# ProPrj___2025-09-23.net
KiCad netlist of a schematic drawn in EasyEDA Pro
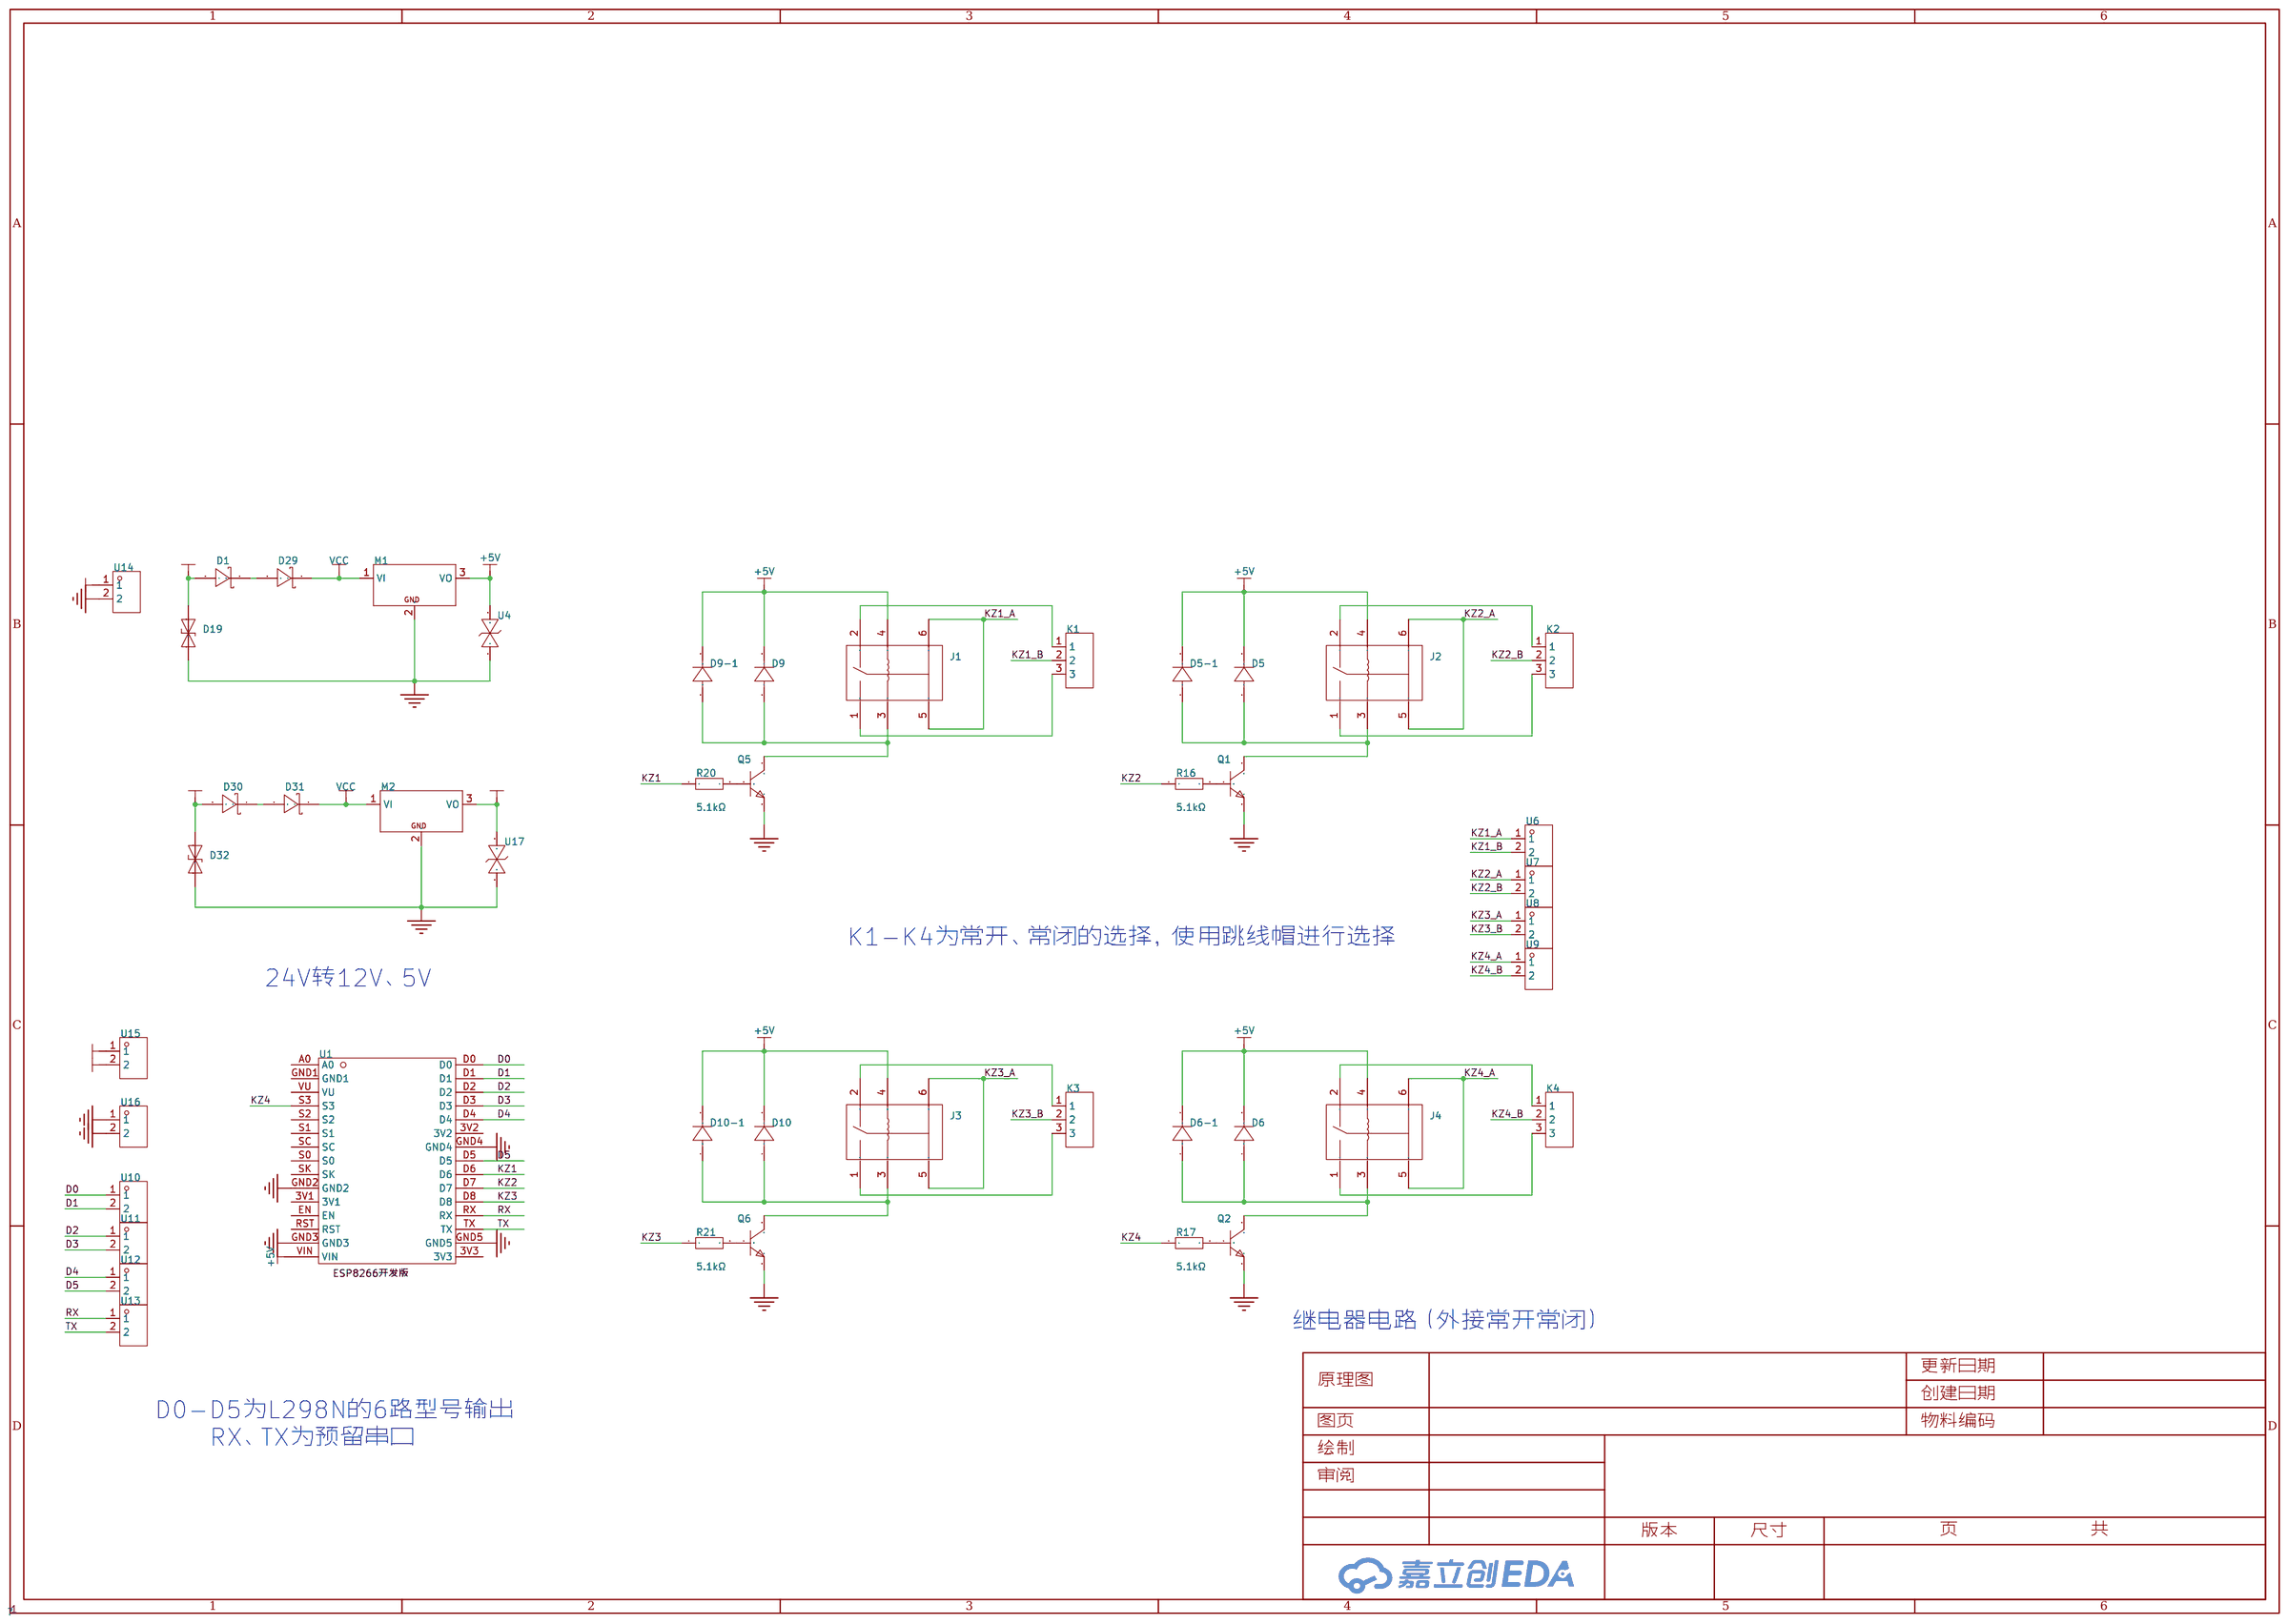
[diagram p0: schematic sheet]

(export (version "E")
  (design (tool "Eeschema 10.0.6"))
  (components
    (comp (ref "D1")
      (value "SS14")
      (footprint "easyedapro:SMA_L4.2-W2.6-LS5.0-RD_1")
      (description "二极管配置:独立式;正向压降(Vf):550mV@1A;直流反向耐压(Vr):40V;整流电流:1A;")
      (fields (field (name "Manufacturer") "MDD(辰达半导体)"))
      (libsource (lib "easyedapro") (part "SS14"))
    )
    (comp (ref "D5")
      (value "1N4148WS")
      (footprint "easyedapro:SOD-323_L1.7-W1.3-LS2.5-FD")
      (description "二极管配置:独立式;正向压降(Vf):1.25V@150mA;直流反向耐压(Vr):100V;整流电流:150mA;反向恢复时间(Trr):4ns;")
      (fields (field (name "Manufacturer") "宏嘉诚"))
      (libsource (lib "easyedapro") (part "1N4148WS_C7420319"))
    )
    (comp (ref "D5-1")
      (value "1N4148WS")
      (footprint "easyedapro:SOD-323_L1.7-W1.3-LS2.5-FD")
      (description "二极管配置:独立式;正向压降(Vf):1.25V@150mA;直流反向耐压(Vr):100V;整流电流:150mA;反向恢复时间(Trr):4ns;")
      (fields (field (name "Manufacturer") "宏嘉诚"))
      (libsource (lib "easyedapro") (part "1N4148WS_C7420319"))
    )
    (comp (ref "D6")
      (value "1N4148WS")
      (footprint "easyedapro:SOD-323_L1.7-W1.3-LS2.5-FD")
      (description "二极管配置:独立式;正向压降(Vf):1.25V@150mA;直流反向耐压(Vr):100V;整流电流:150mA;反向恢复时间(Trr):4ns;")
      (fields (field (name "Manufacturer") "宏嘉诚"))
      (libsource (lib "easyedapro") (part "1N4148WS_C7420319"))
    )
    (comp (ref "D6-1")
      (value "1N4148WS")
      (footprint "easyedapro:SOD-323_L1.7-W1.3-LS2.5-FD")
      (description "二极管配置:独立式;正向压降(Vf):1.25V@150mA;直流反向耐压(Vr):100V;整流电流:150mA;反向恢复时间(Trr):4ns;")
      (fields (field (name "Manufacturer") "宏嘉诚"))
      (libsource (lib "easyedapro") (part "1N4148WS_C7420319"))
    )
    (comp (ref "D9")
      (value "1N4148WS")
      (footprint "easyedapro:SOD-323_L1.7-W1.3-LS2.5-FD")
      (description "二极管配置:独立式;正向压降(Vf):1.25V@150mA;直流反向耐压(Vr):100V;整流电流:150mA;反向恢复时间(Trr):4ns;")
      (fields (field (name "Manufacturer") "宏嘉诚"))
      (libsource (lib "easyedapro") (part "1N4148WS_C7420319"))
    )
    (comp (ref "D9-1")
      (value "1N4148WS")
      (footprint "easyedapro:SOD-323_L1.7-W1.3-LS2.5-FD")
      (description "二极管配置:独立式;正向压降(Vf):1.25V@150mA;直流反向耐压(Vr):100V;整流电流:150mA;反向恢复时间(Trr):4ns;")
      (fields (field (name "Manufacturer") "宏嘉诚"))
      (libsource (lib "easyedapro") (part "1N4148WS_C7420319"))
    )
    (comp (ref "D10")
      (value "1N4148WS")
      (footprint "easyedapro:SOD-323_L1.7-W1.3-LS2.5-FD")
      (description "二极管配置:独立式;正向压降(Vf):1.25V@150mA;直流反向耐压(Vr):100V;整流电流:150mA;反向恢复时间(Trr):4ns;")
      (fields (field (name "Manufacturer") "宏嘉诚"))
      (libsource (lib "easyedapro") (part "1N4148WS_C7420319"))
    )
    (comp (ref "D10-1")
      (value "1N4148WS")
      (footprint "easyedapro:SOD-323_L1.7-W1.3-LS2.5-FD")
      (description "二极管配置:独立式;正向压降(Vf):1.25V@150mA;直流反向耐压(Vr):100V;整流电流:150mA;反向恢复时间(Trr):4ns;")
      (fields (field (name "Manufacturer") "宏嘉诚"))
      (libsource (lib "easyedapro") (part "1N4148WS_C7420319"))
    )
    (comp (ref "D19")
      (value "SMCJ33CA")
      (footprint "easyedapro:SMC_L6.9-W5.9-LS7.9-BI")
      (description "反向截止电压(Vrwm):33V;最大钳位电压:53.3V;峰值脉冲电流(Ipp):28.2A;击穿电压:36.7V;")
      (fields (field (name "Manufacturer") "JJW(捷捷微)"))
      (libsource (lib "easyedapro") (part "SMCJ33CA_C356787"))
    )
    (comp (ref "D29")
      (value "SS14")
      (footprint "easyedapro:SMA_L4.2-W2.6-LS5.0-RD_1")
      (description "二极管配置:独立式;正向压降(Vf):550mV@1A;直流反向耐压(Vr):40V;整流电流:1A;")
      (fields (field (name "Manufacturer") "MDD(辰达半导体)"))
      (libsource (lib "easyedapro") (part "SS14"))
    )
    (comp (ref "D30")
      (value "SS14")
      (footprint "easyedapro:SMA_L4.2-W2.6-LS5.0-RD_1")
      (description "二极管配置:独立式;正向压降(Vf):550mV@1A;直流反向耐压(Vr):40V;整流电流:1A;")
      (fields (field (name "Manufacturer") "MDD(辰达半导体)"))
      (libsource (lib "easyedapro") (part "SS14"))
    )
    (comp (ref "D31")
      (value "SS14")
      (footprint "easyedapro:SMA_L4.2-W2.6-LS5.0-RD_1")
      (description "二极管配置:独立式;正向压降(Vf):550mV@1A;直流反向耐压(Vr):40V;整流电流:1A;")
      (fields (field (name "Manufacturer") "MDD(辰达半导体)"))
      (libsource (lib "easyedapro") (part "SS14"))
    )
    (comp (ref "D32")
      (value "SMCJ33CA")
      (footprint "easyedapro:SMC_L6.9-W5.9-LS7.9-BI")
      (description "反向截止电压(Vrwm):33V;最大钳位电压:53.3V;峰值脉冲电流(Ipp):28.2A;击穿电压:36.7V;")
      (fields (field (name "Manufacturer") "JJW(捷捷微)"))
      (libsource (lib "easyedapro") (part "SMCJ33CA_C356787"))
    )
    (comp (ref "J1")
      (value "HK4100F-DC5V-SHG")
      (footprint "easyedapro:RELAY-TH_HK4100F-DC5V-SHG")
      (description "线圈电压:-;触点形式:-;触点容量(电阻负载):-;最大切换电压:-;最大切换电流:-;")
      (fields (field (name "Manufacturer") "汇科"))
      (libsource (lib "easyedapro") (part "HK4100F-DC5V-SHG"))
    )
    (comp (ref "J2")
      (value "HK4100F-DC5V-SHG")
      (footprint "easyedapro:RELAY-TH_HK4100F-DC5V-SHG")
      (description "线圈电压:-;触点形式:-;触点容量(电阻负载):-;最大切换电压:-;最大切换电流:-;")
      (fields (field (name "Manufacturer") "汇科"))
      (libsource (lib "easyedapro") (part "HK4100F-DC5V-SHG"))
    )
    (comp (ref "J3")
      (value "HK4100F-DC5V-SHG")
      (footprint "easyedapro:RELAY-TH_HK4100F-DC5V-SHG")
      (description "线圈电压:-;触点形式:-;触点容量(电阻负载):-;最大切换电压:-;最大切换电流:-;")
      (fields (field (name "Manufacturer") "汇科"))
      (libsource (lib "easyedapro") (part "HK4100F-DC5V-SHG"))
    )
    (comp (ref "J4")
      (value "HK4100F-DC5V-SHG")
      (footprint "easyedapro:RELAY-TH_HK4100F-DC5V-SHG")
      (description "线圈电压:-;触点形式:-;触点容量(电阻负载):-;最大切换电压:-;最大切换电流:-;")
      (fields (field (name "Manufacturer") "汇科"))
      (libsource (lib "easyedapro") (part "HK4100F-DC5V-SHG"))
    )
    (comp (ref "K1")
      (value "PZ254V-11-03P")
      (footprint "easyedapro:HDR-TH_3P-P2.54-V-M")
      (fields (field (name "Manufacturer") "XFCN(兴飞)"))
      (libsource (lib "easyedapro") (part "PZ254V-11-03P_C2937625"))
    )
    (comp (ref "K2")
      (value "PZ254V-11-03P")
      (footprint "easyedapro:HDR-TH_3P-P2.54-V-M")
      (fields (field (name "Manufacturer") "XFCN(兴飞)"))
      (libsource (lib "easyedapro") (part "PZ254V-11-03P_C2937625"))
    )
    (comp (ref "K3")
      (value "PZ254V-11-03P")
      (footprint "easyedapro:HDR-TH_3P-P2.54-V-M")
      (fields (field (name "Manufacturer") "XFCN(兴飞)"))
      (libsource (lib "easyedapro") (part "PZ254V-11-03P_C2937625"))
    )
    (comp (ref "K4")
      (value "PZ254V-11-03P")
      (footprint "easyedapro:HDR-TH_3P-P2.54-V-M")
      (fields (field (name "Manufacturer") "XFCN(兴飞)"))
      (libsource (lib "easyedapro") (part "PZ254V-11-03P_C2937625"))
    )
    (comp (ref "M1")
      (value "K78L05-1000R3")
      (fields (field (name "Manufacturer") "MORNSUN(金升阳)"))
      (libsource (lib "easyedapro") (part "K7805-2000L"))
    )
    (comp (ref "M2")
      (value "K78L12-1000R3")
      (fields (field (name "Manufacturer") "MORNSUN(金升阳)"))
      (libsource (lib "easyedapro") (part "K7805-2000L"))
    )
    (comp (ref "Q1")
      (value "S9014")
      (footprint "easyedapro:SOT-23-3_L2.9-W1.3-P1.90-LS2.4-BR")
      (description "晶体管类型:NPN;集电极电流(Ic):100mA;集射极击穿电压(Vceo):45V;耗散功率(Pd):200mW;直流电流增益(hFE):200@1mA,5V;")
      (fields (field (name "Manufacturer") "CJ(江苏长电/长晶)"))
      (libsource (lib "easyedapro") (part "S9014LT1 (S9014 J6)"))
    )
    (comp (ref "Q2")
      (value "S9014")
      (footprint "easyedapro:SOT-23-3_L2.9-W1.3-P1.90-LS2.4-BR")
      (description "晶体管类型:NPN;集电极电流(Ic):100mA;集射极击穿电压(Vceo):45V;耗散功率(Pd):200mW;直流电流增益(hFE):200@1mA,5V;")
      (fields (field (name "Manufacturer") "CJ(江苏长电/长晶)"))
      (libsource (lib "easyedapro") (part "S9014LT1 (S9014 J6)"))
    )
    (comp (ref "Q5")
      (value "S9014")
      (footprint "easyedapro:SOT-23-3_L2.9-W1.3-P1.90-LS2.4-BR")
      (description "晶体管类型:NPN;集电极电流(Ic):100mA;集射极击穿电压(Vceo):45V;耗散功率(Pd):200mW;直流电流增益(hFE):200@1mA,5V;")
      (fields (field (name "Manufacturer") "CJ(江苏长电/长晶)"))
      (libsource (lib "easyedapro") (part "S9014LT1 (S9014 J6)"))
    )
    (comp (ref "Q6")
      (value "S9014")
      (footprint "easyedapro:SOT-23-3_L2.9-W1.3-P1.90-LS2.4-BR")
      (description "晶体管类型:NPN;集电极电流(Ic):100mA;集射极击穿电压(Vceo):45V;耗散功率(Pd):200mW;直流电流增益(hFE):200@1mA,5V;")
      (fields (field (name "Manufacturer") "CJ(江苏长电/长晶)"))
      (libsource (lib "easyedapro") (part "S9014LT1 (S9014 J6)"))
    )
    (comp (ref "R16")
      (value "5.1kΩ")
      (fields
        (field (name "Manufacturer Part") "0603WAF5101T5E")
        (field (name "Manufacturer") "UNI-ROYAL(厚声)")
      )
      (libsource (lib "easyedapro") (part "电阻"))
    )
    (comp (ref "R17")
      (value "5.1kΩ")
      (fields
        (field (name "Manufacturer Part") "0603WAF5101T5E")
        (field (name "Manufacturer") "UNI-ROYAL(厚声)")
      )
      (libsource (lib "easyedapro") (part "电阻"))
    )
    (comp (ref "R20")
      (value "5.1kΩ")
      (fields
        (field (name "Manufacturer Part") "0603WAF5101T5E")
        (field (name "Manufacturer") "UNI-ROYAL(厚声)")
      )
      (libsource (lib "easyedapro") (part "电阻"))
    )
    (comp (ref "R21")
      (value "5.1kΩ")
      (fields
        (field (name "Manufacturer Part") "0603WAF5101T5E")
        (field (name "Manufacturer") "UNI-ROYAL(厚声)")
      )
      (libsource (lib "easyedapro") (part "电阻"))
    )
    (comp (ref "U1")
      (value "~")
      (footprint "easyedapro:ESP8266开发板")
      (libsource (lib "easyedapro") (part "ESP8266开发板"))
    )
    (comp (ref "U4")
      (value "SMBJ5.0CA")
      (footprint "easyedapro:SMB_L4.5-W3.6-LS5.2-BI")
      (description "极性:双向;反向截止电压(Vrwm):5V;钳位电压:9.2V;峰值脉冲电流(Ipp):65.22A;峰值脉冲功率(Ppp):600W;击穿电压:7V;")
      (fields (field (name "Manufacturer") "宏嘉诚"))
      (libsource (lib "easyedapro") (part "SMBJ5.0CA_C19077559"))
    )
    (comp (ref "U6")
      (value "KF7.62-2P(green)")
      (fields (field (name "Manufacturer") "KEFA(科发)"))
      (libsource (lib "easyedapro") (part "KF8500-8.5-2P"))
    )
    (comp (ref "U7")
      (value "KF7.62-2P(green)")
      (fields (field (name "Manufacturer") "KEFA(科发)"))
      (libsource (lib "easyedapro") (part "KF8500-8.5-2P"))
    )
    (comp (ref "U8")
      (value "KF7.62-2P(green)")
      (fields (field (name "Manufacturer") "KEFA(科发)"))
      (libsource (lib "easyedapro") (part "KF8500-8.5-2P"))
    )
    (comp (ref "U9")
      (value "KF7.62-2P(green)")
      (fields (field (name "Manufacturer") "KEFA(科发)"))
      (libsource (lib "easyedapro") (part "KF8500-8.5-2P"))
    )
    (comp (ref "U10")
      (value "KF7.62-2P(green)")
      (fields (field (name "Manufacturer") "KEFA(科发)"))
      (libsource (lib "easyedapro") (part "KF8500-8.5-2P"))
    )
    (comp (ref "U11")
      (value "KF7.62-2P(green)")
      (fields (field (name "Manufacturer") "KEFA(科发)"))
      (libsource (lib "easyedapro") (part "KF8500-8.5-2P"))
    )
    (comp (ref "U12")
      (value "KF7.62-2P(green)")
      (fields (field (name "Manufacturer") "KEFA(科发)"))
      (libsource (lib "easyedapro") (part "KF8500-8.5-2P"))
    )
    (comp (ref "U13")
      (value "KF7.62-2P(green)")
      (fields (field (name "Manufacturer") "KEFA(科发)"))
      (libsource (lib "easyedapro") (part "KF8500-8.5-2P"))
    )
    (comp (ref "U14")
      (value "KF7.62-2P(green)")
      (fields (field (name "Manufacturer") "KEFA(科发)"))
      (libsource (lib "easyedapro") (part "KF8500-8.5-2P"))
    )
    (comp (ref "U15")
      (value "KF7.62-2P(green)")
      (fields (field (name "Manufacturer") "KEFA(科发)"))
      (libsource (lib "easyedapro") (part "KF8500-8.5-2P"))
    )
    (comp (ref "U16")
      (value "KF7.62-2P(green)")
      (fields (field (name "Manufacturer") "KEFA(科发)"))
      (libsource (lib "easyedapro") (part "KF8500-8.5-2P"))
    )
    (comp (ref "U17")
      (value "SMBJ12CA")
      (footprint "easyedapro:SMB_L4.5-W3.6-LS5.2-BI")
      (description "极性:双向;反向截止电压(Vrwm):5V;钳位电压:9.2V;峰值脉冲电流(Ipp):65.22A;峰值脉冲功率(Ppp):600W;击穿电压:7V;")
      (fields (field (name "Manufacturer") "Littelfuse(美国力特)"))
      (libsource (lib "easyedapro") (part "SMBJ5.0CA_C19077559"))
    )
  )
  (nets
    (net (code "1") (name "+5V") (class "Default")
      (node (ref "D10") (pin "2") (pinfunction "K_2") (pintype "unspecified"))
      (node (ref "D10-1") (pin "2") (pinfunction "K_2") (pintype "unspecified"))
      (node (ref "D5") (pin "2") (pinfunction "K_2") (pintype "unspecified"))
      (node (ref "D5-1") (pin "2") (pinfunction "K_2") (pintype "unspecified"))
      (node (ref "D6") (pin "2") (pinfunction "K_2") (pintype "unspecified"))
      (node (ref "D6-1") (pin "2") (pinfunction "K_2") (pintype "unspecified"))
      (node (ref "D9") (pin "2") (pinfunction "K_2") (pintype "unspecified"))
      (node (ref "D9-1") (pin "2") (pinfunction "K_2") (pintype "unspecified"))
      (node (ref "J1") (pin "4") (pinfunction "4_4") (pintype "unspecified"))
      (node (ref "J2") (pin "4") (pinfunction "4_4") (pintype "unspecified"))
      (node (ref "J3") (pin "4") (pinfunction "4_4") (pintype "unspecified"))
      (node (ref "J4") (pin "4") (pinfunction "4_4") (pintype "unspecified"))
      (node (ref "M1") (pin "3") (pinfunction "VO_3") (pintype "unspecified"))
      (node (ref "U1") (pin "VIN") (pinfunction "VIN_VIN") (pintype "input"))
      (node (ref "U4") (pin "2") (pinfunction "2_2") (pintype "unspecified"))
    )
    (net (code "2") (name "+12V") (class "Default")
      (node (ref "M2") (pin "3") (pinfunction "VO_3") (pintype "unspecified"))
      (node (ref "U15") (pin "1") (pinfunction "1_1") (pintype "unspecified"))
      (node (ref "U15") (pin "2") (pinfunction "2_2") (pintype "unspecified"))
      (node (ref "U17") (pin "2") (pinfunction "2_2") (pintype "unspecified"))
    )
    (net (code "3") (name "+24V") (class "Default")
      (node (ref "D1") (pin "2") (pinfunction "A_2") (pintype "unspecified"))
      (node (ref "D19") (pin "2") (pinfunction "A_2") (pintype "unspecified"))
      (node (ref "D30") (pin "2") (pinfunction "A_2") (pintype "unspecified"))
      (node (ref "D32") (pin "2") (pinfunction "A_2") (pintype "unspecified"))
      (node (ref "U14") (pin "1") (pinfunction "1_1") (pintype "unspecified"))
    )
    (net (code "4") (name "/D0") (class "Default")
      (node (ref "U1") (pin "D0") (pinfunction "D0_D0") (pintype "input"))
      (node (ref "U10") (pin "1") (pinfunction "1_1") (pintype "unspecified"))
    )
    (net (code "5") (name "/D1") (class "Default")
      (node (ref "U1") (pin "D1") (pinfunction "D1_D1") (pintype "input"))
      (node (ref "U10") (pin "2") (pinfunction "2_2") (pintype "unspecified"))
    )
    (net (code "6") (name "/D2") (class "Default")
      (node (ref "U1") (pin "D2") (pinfunction "D2_D2") (pintype "input"))
      (node (ref "U11") (pin "1") (pinfunction "1_1") (pintype "unspecified"))
    )
    (net (code "7") (name "/D3") (class "Default")
      (node (ref "U1") (pin "D3") (pinfunction "D3_D3") (pintype "input"))
      (node (ref "U11") (pin "2") (pinfunction "2_2") (pintype "unspecified"))
    )
    (net (code "8") (name "/D4") (class "Default")
      (node (ref "U1") (pin "D4") (pinfunction "D4_D4") (pintype "input"))
      (node (ref "U12") (pin "1") (pinfunction "1_1") (pintype "unspecified"))
    )
    (net (code "9") (name "/D5") (class "Default")
      (node (ref "U1") (pin "D5") (pinfunction "D5_D5") (pintype "input"))
      (node (ref "U12") (pin "2") (pinfunction "2_2") (pintype "unspecified"))
    )
    (net (code "10") (name "/KZ1") (class "Default")
      (node (ref "R20") (pin "1") (pinfunction "1_1") (pintype "input"))
      (node (ref "U1") (pin "D6") (pinfunction "D6_D6") (pintype "input"))
    )
    (net (code "11") (name "/KZ1_A") (class "Default")
      (node (ref "J1") (pin "5") (pinfunction "5_5") (pintype "unspecified"))
      (node (ref "J1") (pin "6") (pinfunction "6_6") (pintype "unspecified"))
      (node (ref "U6") (pin "1") (pinfunction "1_1") (pintype "unspecified"))
    )
    (net (code "12") (name "/KZ1_B") (class "Default")
      (node (ref "K1") (pin "2") (pinfunction "2_2") (pintype "unspecified"))
      (node (ref "U6") (pin "2") (pinfunction "2_2") (pintype "unspecified"))
    )
    (net (code "13") (name "/KZ2") (class "Default")
      (node (ref "R16") (pin "1") (pinfunction "1_1") (pintype "input"))
      (node (ref "U1") (pin "D7") (pinfunction "D7_D7") (pintype "input"))
    )
    (net (code "14") (name "/KZ2_A") (class "Default")
      (node (ref "J2") (pin "5") (pinfunction "5_5") (pintype "unspecified"))
      (node (ref "J2") (pin "6") (pinfunction "6_6") (pintype "unspecified"))
      (node (ref "U7") (pin "1") (pinfunction "1_1") (pintype "unspecified"))
    )
    (net (code "15") (name "/KZ2_B") (class "Default")
      (node (ref "K2") (pin "2") (pinfunction "2_2") (pintype "unspecified"))
      (node (ref "U7") (pin "2") (pinfunction "2_2") (pintype "unspecified"))
    )
    (net (code "16") (name "/KZ3") (class "Default")
      (node (ref "R21") (pin "1") (pinfunction "1_1") (pintype "input"))
      (node (ref "U1") (pin "D8") (pinfunction "D8_D8") (pintype "input"))
    )
    (net (code "17") (name "/KZ3_A") (class "Default")
      (node (ref "J3") (pin "5") (pinfunction "5_5") (pintype "unspecified"))
      (node (ref "J3") (pin "6") (pinfunction "6_6") (pintype "unspecified"))
      (node (ref "U8") (pin "1") (pinfunction "1_1") (pintype "unspecified"))
    )
    (net (code "18") (name "/KZ3_B") (class "Default")
      (node (ref "K3") (pin "2") (pinfunction "2_2") (pintype "unspecified"))
      (node (ref "U8") (pin "2") (pinfunction "2_2") (pintype "unspecified"))
    )
    (net (code "19") (name "/KZ4") (class "Default")
      (node (ref "R17") (pin "1") (pinfunction "1_1") (pintype "input"))
      (node (ref "U1") (pin "S3") (pinfunction "S3_S3") (pintype "input"))
    )
    (net (code "20") (name "/KZ4_A") (class "Default")
      (node (ref "J4") (pin "5") (pinfunction "5_5") (pintype "unspecified"))
      (node (ref "J4") (pin "6") (pinfunction "6_6") (pintype "unspecified"))
      (node (ref "U9") (pin "1") (pinfunction "1_1") (pintype "unspecified"))
    )
    (net (code "21") (name "/KZ4_B") (class "Default")
      (node (ref "K4") (pin "2") (pinfunction "2_2") (pintype "unspecified"))
      (node (ref "U9") (pin "2") (pinfunction "2_2") (pintype "unspecified"))
    )
    (net (code "22") (name "/RX") (class "Default")
      (node (ref "U1") (pin "RX") (pinfunction "RX_RX") (pintype "input"))
      (node (ref "U13") (pin "1") (pinfunction "1_1") (pintype "unspecified"))
    )
    (net (code "23") (name "/TX") (class "Default")
      (node (ref "U1") (pin "TX") (pinfunction "TX_TX") (pintype "input"))
      (node (ref "U13") (pin "2") (pinfunction "2_2") (pintype "unspecified"))
    )
    (net (code "24") (name "GND") (class "Default")
      (node (ref "D19") (pin "1") (pinfunction "K_1") (pintype "unspecified"))
      (node (ref "D32") (pin "1") (pinfunction "K_1") (pintype "unspecified"))
      (node (ref "M1") (pin "2") (pinfunction "GND_2") (pintype "unspecified"))
      (node (ref "M2") (pin "2") (pinfunction "GND_2") (pintype "unspecified"))
      (node (ref "Q1") (pin "2") (pinfunction "E_2") (pintype "unspecified"))
      (node (ref "Q2") (pin "2") (pinfunction "E_2") (pintype "unspecified"))
      (node (ref "Q5") (pin "2") (pinfunction "E_2") (pintype "unspecified"))
      (node (ref "Q6") (pin "2") (pinfunction "E_2") (pintype "unspecified"))
      (node (ref "U1") (pin "GND2") (pinfunction "GND2_GND2") (pintype "input"))
      (node (ref "U1") (pin "GND3") (pinfunction "GND3_GND3") (pintype "input"))
      (node (ref "U1") (pin "GND4") (pinfunction "GND4_GND4") (pintype "input"))
      (node (ref "U1") (pin "GND5") (pinfunction "GND5_GND5") (pintype "input"))
      (node (ref "U14") (pin "2") (pinfunction "2_2") (pintype "unspecified"))
      (node (ref "U16") (pin "1") (pinfunction "1_1") (pintype "unspecified"))
      (node (ref "U16") (pin "2") (pinfunction "2_2") (pintype "unspecified"))
      (node (ref "U17") (pin "1") (pinfunction "1_1") (pintype "unspecified"))
      (node (ref "U4") (pin "1") (pinfunction "1_1") (pintype "unspecified"))
    )
    (net (code "25") (name "Net-(D1-K)") (class "Default")
      (node (ref "D1") (pin "1") (pinfunction "K_1") (pintype "unspecified"))
      (node (ref "D29") (pin "2") (pinfunction "A_2") (pintype "unspecified"))
    )
    (net (code "26") (name "Net-(D5-1-A)") (class "Default")
      (node (ref "D5") (pin "1") (pinfunction "A_1") (pintype "unspecified"))
      (node (ref "D5-1") (pin "1") (pinfunction "A_1") (pintype "unspecified"))
      (node (ref "J2") (pin "3") (pinfunction "3_3") (pintype "unspecified"))
      (node (ref "Q1") (pin "3") (pinfunction "C_3") (pintype "unspecified"))
    )
    (net (code "27") (name "Net-(D6-1-A)") (class "Default")
      (node (ref "D6") (pin "1") (pinfunction "A_1") (pintype "unspecified"))
      (node (ref "D6-1") (pin "1") (pinfunction "A_1") (pintype "unspecified"))
      (node (ref "J4") (pin "3") (pinfunction "3_3") (pintype "unspecified"))
      (node (ref "Q2") (pin "3") (pinfunction "C_3") (pintype "unspecified"))
    )
    (net (code "28") (name "Net-(D9-1-A)") (class "Default")
      (node (ref "D9") (pin "1") (pinfunction "A_1") (pintype "unspecified"))
      (node (ref "D9-1") (pin "1") (pinfunction "A_1") (pintype "unspecified"))
      (node (ref "J1") (pin "3") (pinfunction "3_3") (pintype "unspecified"))
      (node (ref "Q5") (pin "3") (pinfunction "C_3") (pintype "unspecified"))
    )
    (net (code "29") (name "Net-(D10-1-A)") (class "Default")
      (node (ref "D10") (pin "1") (pinfunction "A_1") (pintype "unspecified"))
      (node (ref "D10-1") (pin "1") (pinfunction "A_1") (pintype "unspecified"))
      (node (ref "J3") (pin "3") (pinfunction "3_3") (pintype "unspecified"))
      (node (ref "Q6") (pin "3") (pinfunction "C_3") (pintype "unspecified"))
    )
    (net (code "30") (name "Net-(D30-K)") (class "Default")
      (node (ref "D30") (pin "1") (pinfunction "K_1") (pintype "unspecified"))
      (node (ref "D31") (pin "2") (pinfunction "A_2") (pintype "unspecified"))
    )
    (net (code "31") (name "Net-(J1-Pad1)") (class "Default")
      (node (ref "J1") (pin "1") (pinfunction "1_1") (pintype "unspecified"))
      (node (ref "K1") (pin "3") (pinfunction "3_3") (pintype "unspecified"))
    )
    (net (code "32") (name "Net-(J1-Pad2)") (class "Default")
      (node (ref "J1") (pin "2") (pinfunction "2_2") (pintype "unspecified"))
      (node (ref "K1") (pin "1") (pinfunction "1_1") (pintype "unspecified"))
    )
    (net (code "33") (name "Net-(J2-Pad1)") (class "Default")
      (node (ref "J2") (pin "1") (pinfunction "1_1") (pintype "unspecified"))
      (node (ref "K2") (pin "3") (pinfunction "3_3") (pintype "unspecified"))
    )
    (net (code "34") (name "Net-(J2-Pad2)") (class "Default")
      (node (ref "J2") (pin "2") (pinfunction "2_2") (pintype "unspecified"))
      (node (ref "K2") (pin "1") (pinfunction "1_1") (pintype "unspecified"))
    )
    (net (code "35") (name "Net-(J3-Pad1)") (class "Default")
      (node (ref "J3") (pin "1") (pinfunction "1_1") (pintype "unspecified"))
      (node (ref "K3") (pin "3") (pinfunction "3_3") (pintype "unspecified"))
    )
    (net (code "36") (name "Net-(J3-Pad2)") (class "Default")
      (node (ref "J3") (pin "2") (pinfunction "2_2") (pintype "unspecified"))
      (node (ref "K3") (pin "1") (pinfunction "1_1") (pintype "unspecified"))
    )
    (net (code "37") (name "Net-(J4-Pad1)") (class "Default")
      (node (ref "J4") (pin "1") (pinfunction "1_1") (pintype "unspecified"))
      (node (ref "K4") (pin "3") (pinfunction "3_3") (pintype "unspecified"))
    )
    (net (code "38") (name "Net-(J4-Pad2)") (class "Default")
      (node (ref "J4") (pin "2") (pinfunction "2_2") (pintype "unspecified"))
      (node (ref "K4") (pin "1") (pinfunction "1_1") (pintype "unspecified"))
    )
    (net (code "39") (name "Net-(Q1-B)") (class "Default")
      (node (ref "Q1") (pin "1") (pinfunction "B_1") (pintype "unspecified"))
      (node (ref "R16") (pin "2") (pinfunction "2_2") (pintype "input"))
    )
    (net (code "40") (name "Net-(Q2-B)") (class "Default")
      (node (ref "Q2") (pin "1") (pinfunction "B_1") (pintype "unspecified"))
      (node (ref "R17") (pin "2") (pinfunction "2_2") (pintype "input"))
    )
    (net (code "41") (name "Net-(Q5-B)") (class "Default")
      (node (ref "Q5") (pin "1") (pinfunction "B_1") (pintype "unspecified"))
      (node (ref "R20") (pin "2") (pinfunction "2_2") (pintype "input"))
    )
    (net (code "42") (name "Net-(Q6-B)") (class "Default")
      (node (ref "Q6") (pin "1") (pinfunction "B_1") (pintype "unspecified"))
      (node (ref "R21") (pin "2") (pinfunction "2_2") (pintype "input"))
    )
    (net (code "43") (name "VCC") (class "Default")
      (node (ref "D29") (pin "1") (pinfunction "K_1") (pintype "unspecified"))
      (node (ref "D31") (pin "1") (pinfunction "K_1") (pintype "unspecified"))
      (node (ref "M1") (pin "1") (pinfunction "VI_1") (pintype "input"))
      (node (ref "M2") (pin "1") (pinfunction "VI_1") (pintype "input"))
    )
    (net (code "44") (name "unconnected-(U1-Pad3V1)") (class "Default")
      (node (ref "U1") (pin "3V1") (pinfunction "3V1_3V1") (pintype "input"))
    )
    (net (code "45") (name "unconnected-(U1-Pad3V2)") (class "Default")
      (node (ref "U1") (pin "3V2") (pinfunction "3V2_3V2") (pintype "input"))
    )
    (net (code "46") (name "unconnected-(U1-Pad3V3)") (class "Default")
      (node (ref "U1") (pin "3V3") (pinfunction "3V3_3V3") (pintype "input"))
    )
    (net (code "47") (name "unconnected-(U1-PadA0)") (class "Default")
      (node (ref "U1") (pin "A0") (pinfunction "A0_A0") (pintype "input"))
    )
    (net (code "48") (name "unconnected-(U1-PadEN)") (class "Default")
      (node (ref "U1") (pin "EN") (pinfunction "EN_EN") (pintype "input"))
    )
    (net (code "49") (name "unconnected-(U1-PadGND1)") (class "Default")
      (node (ref "U1") (pin "GND1") (pinfunction "GND1_GND1") (pintype "input"))
    )
    (net (code "50") (name "unconnected-(U1-PadRST)") (class "Default")
      (node (ref "U1") (pin "RST") (pinfunction "RST_RST") (pintype "input"))
    )
    (net (code "51") (name "unconnected-(U1-PadS0)") (class "Default")
      (node (ref "U1") (pin "S0") (pinfunction "S0_S0") (pintype "input"))
    )
    (net (code "52") (name "unconnected-(U1-PadS1)") (class "Default")
      (node (ref "U1") (pin "S1") (pinfunction "S1_S1") (pintype "input"))
    )
    (net (code "53") (name "unconnected-(U1-PadS2)") (class "Default")
      (node (ref "U1") (pin "S2") (pinfunction "S2_S2") (pintype "input"))
    )
    (net (code "54") (name "unconnected-(U1-PadSC)") (class "Default")
      (node (ref "U1") (pin "SC") (pinfunction "SC_SC") (pintype "input"))
    )
    (net (code "55") (name "unconnected-(U1-PadSK)") (class "Default")
      (node (ref "U1") (pin "SK") (pinfunction "SK_SK") (pintype "input"))
    )
    (net (code "56") (name "unconnected-(U1-PadVU)") (class "Default")
      (node (ref "U1") (pin "VU") (pinfunction "VU_VU") (pintype "input"))
    )
  )
)
